# ss_emg.net
KiCad netlist of a schematic drawn in EAGLE
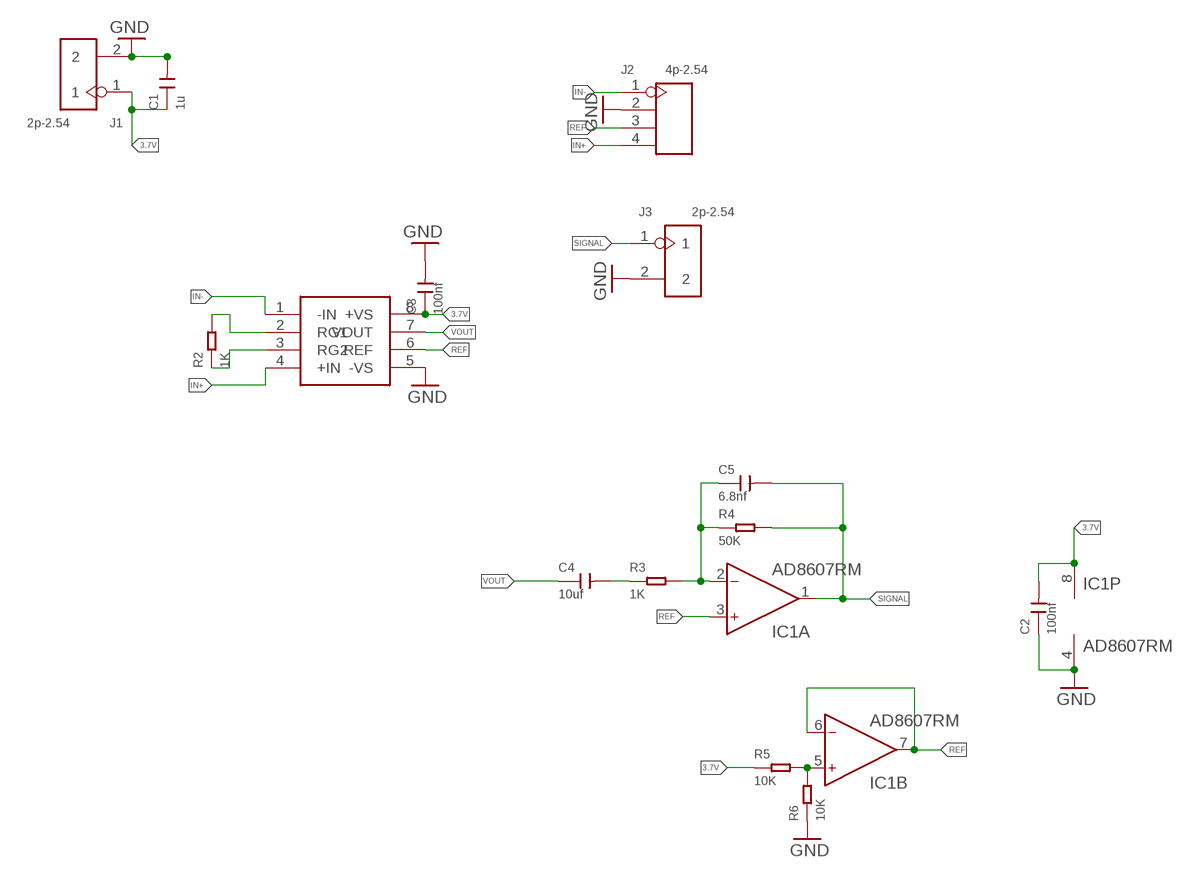
[diagram p0: schematic, sheet 1]

(export (version "E")
  (design (tool "Eeschema 10.0.6"))
  (components
    (comp (ref "C1")
      (value "1u")
      (footprint "eagle-import:C0402")
      (fields (field (name "MPN") "GRM1555C1H1R8BA01D"))
      (libsource (lib "eagle-import") (part "CERAMIC-1.8PF-50V-0.1PF-NPO(0402)"))
    )
    (comp (ref "C2")
      (value "100nf")
      (footprint "eagle-import:C0402")
      (fields (field (name "MPN") "GRM1555C1H1R8BA01D"))
      (libsource (lib "eagle-import") (part "CERAMIC-1.8PF-50V-0.1PF-NPO(0402)"))
    )
    (comp (ref "C3")
      (value "100nf")
      (footprint "eagle-import:C0402")
      (fields (field (name "MPN") "GRM1555C1H1R8BA01D"))
      (libsource (lib "eagle-import") (part "CERAMIC-1.8PF-50V-0.1PF-NPO(0402)"))
    )
    (comp (ref "C4")
      (value "10uf")
      (footprint "eagle-import:C0402")
      (fields (field (name "MPN") "GRM1555C1H1R8BA01D"))
      (libsource (lib "eagle-import") (part "CERAMIC-1.8PF-50V-0.1PF-NPO(0402)"))
    )
    (comp (ref "C5")
      (value "6.8nf")
      (footprint "eagle-import:C0402")
      (fields (field (name "MPN") "GRM1555C1H1R8BA01D"))
      (libsource (lib "eagle-import") (part "CERAMIC-1.8PF-50V-0.1PF-NPO(0402)"))
    )
    (comp (ref "IC1")
      (value "AD8607RM")
      (footprint "eagle-import:MSOP08")
      (fields (field (name "MF") "ALTERA CORPORATION") (field (name "MPN") "AD8607ARMZ-REEL"))
      (libsource (lib "eagle-import") (part "AD8607RM"))
    )
    (comp (ref "J1")
      (value "2p-2.54")
      (footprint "eagle-import:H2-2.54")
      (fields (field (name "MPN") "F185-1102A1BSYA1"))
      (libsource (lib "eagle-import") (part "DIP-BLACK-FEMALE-HEADER-VERT(2P-2.54)"))
    )
    (comp (ref "J2")
      (value "4p-2.54")
      (footprint "eagle-import:H4-2.54")
      (fields (field (name "MPN") "F185-1104A1BSYA1"))
      (libsource (lib "eagle-import") (part "DIP-BLACK-FEMALE-HEADER-VERT(4P-2.54)"))
    )
    (comp (ref "J3")
      (value "2p-2.54")
      (footprint "eagle-import:H2-2.54")
      (fields (field (name "MPN") "F185-1102A1BSYA1"))
      (libsource (lib "eagle-import") (part "DIP-BLACK-FEMALE-HEADER-VERT(2P-2.54)"))
    )
    (comp (ref "R2")
      (value "1K")
      (footprint "eagle-import:R0402")
      (fields (field (name "MPN") "RC0402JR-071KL"))
      (libsource (lib "eagle-import") (part "SMD-RES-1K-5%-1/16W(0402)"))
    )
    (comp (ref "R3")
      (value "1K")
      (footprint "eagle-import:R0402")
      (fields (field (name "MPN") "RC0402JR-071KL"))
      (libsource (lib "eagle-import") (part "SMD-RES-1K-5%-1/16W(0402)"))
    )
    (comp (ref "R4")
      (value "50K")
      (footprint "eagle-import:R0402")
      (fields (field (name "MPN") "RC0402JR-071KL"))
      (libsource (lib "eagle-import") (part "SMD-RES-1K-5%-1/16W(0402)"))
    )
    (comp (ref "R5")
      (value "10K")
      (footprint "eagle-import:R0402")
      (fields (field (name "MPN") "RC0402JR-071KL"))
      (libsource (lib "eagle-import") (part "SMD-RES-1K-5%-1/16W(0402)"))
    )
    (comp (ref "R6")
      (value "10K")
      (footprint "eagle-import:R0402")
      (fields (field (name "MPN") "RC0402JR-071KL"))
      (libsource (lib "eagle-import") (part "SMD-RES-1K-5%-1/16W(0402)"))
    )
    (comp (ref "U$1")
      (value "AD8221")
      (footprint "eagle-import:MSOP08")
      (libsource (lib "eagle-import") (part "AD8221"))
    )
  )
  (nets
    (net (code "1") (name "3.7V") (class "Default")
      (node (ref "C1") (pin "1") (pinfunction "1_1") (pintype "passive"))
      (node (ref "C2") (pin "2") (pinfunction "2_2") (pintype "passive"))
      (node (ref "C3") (pin "1") (pinfunction "1_1") (pintype "passive"))
      (node (ref "IC1") (pin "8") (pinfunction "V+_8") (pintype "power_in"))
      (node (ref "J1") (pin "1") (pinfunction "1_1") (pintype "bidirectional"))
      (node (ref "R5") (pin "1") (pinfunction "1_1") (pintype "passive"))
      (node (ref "U$1") (pin "8") (pinfunction "+VS_8") (pintype "bidirectional"))
    )
    (net (code "2") (name "GND") (class "Default")
      (node (ref "C1") (pin "2") (pinfunction "2_2") (pintype "passive"))
      (node (ref "C2") (pin "1") (pinfunction "1_1") (pintype "passive"))
      (node (ref "C3") (pin "2") (pinfunction "2_2") (pintype "passive"))
      (node (ref "IC1") (pin "4") (pinfunction "V-_4") (pintype "power_in"))
      (node (ref "J1") (pin "2") (pinfunction "2_2") (pintype "bidirectional"))
      (node (ref "J2") (pin "2") (pinfunction "P$2_2") (pintype "bidirectional"))
      (node (ref "J3") (pin "2") (pinfunction "2_2") (pintype "bidirectional"))
      (node (ref "R6") (pin "1") (pinfunction "1_1") (pintype "passive"))
      (node (ref "U$1") (pin "5") (pinfunction "-VS_5") (pintype "bidirectional"))
    )
    (net (code "3") (name "IN+") (class "Default")
      (node (ref "J2") (pin "4") (pinfunction "P$4_4") (pintype "bidirectional"))
      (node (ref "U$1") (pin "4") (pinfunction "+IN_4") (pintype "bidirectional"))
    )
    (net (code "4") (name "IN-") (class "Default")
      (node (ref "J2") (pin "1") (pinfunction "P$1_1") (pintype "bidirectional"))
      (node (ref "U$1") (pin "1") (pinfunction "-IN_1") (pintype "bidirectional"))
    )
    (net (code "5") (name "Net-(C4-Pad2)") (class "Default")
      (node (ref "C4") (pin "2") (pinfunction "2_2") (pintype "passive"))
      (node (ref "R3") (pin "1") (pinfunction "1_1") (pintype "passive"))
    )
    (net (code "6") (name "Net-(IC1A-IN-)") (class "Default")
      (node (ref "C5") (pin "1") (pinfunction "1_1") (pintype "passive"))
      (node (ref "IC1") (pin "2") (pinfunction "IN-_2") (pintype "input"))
      (node (ref "R3") (pin "2") (pinfunction "2_2") (pintype "passive"))
      (node (ref "R4") (pin "1") (pinfunction "1_1") (pintype "passive"))
    )
    (net (code "7") (name "Net-(IC1B-IN+)") (class "Default")
      (node (ref "IC1") (pin "5") (pinfunction "IN+_5") (pintype "input"))
      (node (ref "R5") (pin "2") (pinfunction "2_2") (pintype "passive"))
      (node (ref "R6") (pin "2") (pinfunction "2_2") (pintype "passive"))
    )
    (net (code "8") (name "Net-(U$1-RG1)") (class "Default")
      (node (ref "R2") (pin "2") (pinfunction "2_2") (pintype "passive"))
      (node (ref "U$1") (pin "2") (pinfunction "RG1_2") (pintype "bidirectional"))
    )
    (net (code "9") (name "Net-(U$1-RG2)") (class "Default")
      (node (ref "R2") (pin "1") (pinfunction "1_1") (pintype "passive"))
      (node (ref "U$1") (pin "3") (pinfunction "RG2_3") (pintype "bidirectional"))
    )
    (net (code "10") (name "REF") (class "Default")
      (node (ref "IC1") (pin "3") (pinfunction "IN+_3") (pintype "input"))
      (node (ref "IC1") (pin "6") (pinfunction "IN-_6") (pintype "input"))
      (node (ref "IC1") (pin "7") (pinfunction "OUT_7") (pintype "output"))
      (node (ref "J2") (pin "3") (pinfunction "P$3_3") (pintype "bidirectional"))
      (node (ref "U$1") (pin "6") (pinfunction "REF_6") (pintype "bidirectional"))
    )
    (net (code "11") (name "SIGNAL") (class "Default")
      (node (ref "C5") (pin "2") (pinfunction "2_2") (pintype "passive"))
      (node (ref "IC1") (pin "1") (pinfunction "OUT_1") (pintype "output"))
      (node (ref "J3") (pin "1") (pinfunction "1_1") (pintype "bidirectional"))
      (node (ref "R4") (pin "2") (pinfunction "2_2") (pintype "passive"))
    )
    (net (code "12") (name "VOUT") (class "Default")
      (node (ref "C4") (pin "1") (pinfunction "1_1") (pintype "passive"))
      (node (ref "U$1") (pin "7") (pinfunction "VOUT_7") (pintype "bidirectional"))
    )
  )
)
